# PWR.net
KiCad netlist of a schematic drawn in Altium Designer
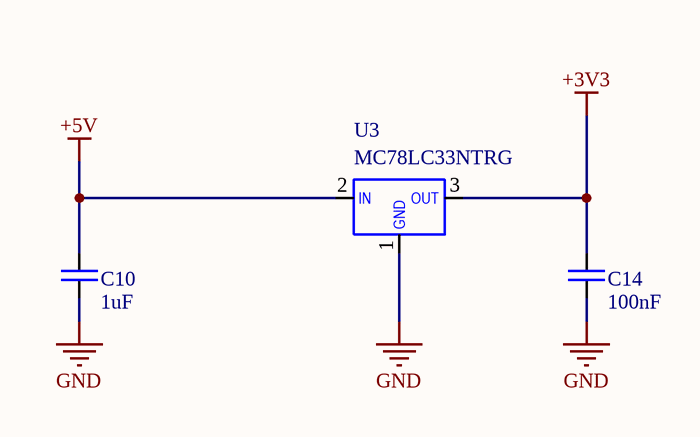
[diagram p0: PWR.SchDoc]

(export (version "E")
  (design (tool "Eeschema 10.0.6"))
  (components
    (comp (ref "C10")
      (value "1uF")
      (footprint "CAP_0603")
      (description "None polar capacitor")
      (libsource (lib "DISCRETE") (part "C_NONE_POLAR"))
    )
    (comp (ref "C14")
      (value "100nF")
      (footprint "CAP_0603")
      (description "None polar capacitor")
      (libsource (lib "DISCRETE") (part "C_NONE_POLAR"))
    )
    (comp (ref "U3")
      (value "MC78LC33NTRG")
      (footprint "ICs:SOT753")
      (description "Low dropout Linear Voltage Regulator")
      (libsource (lib "ICs") (part "MC78LC33NTRG"))
    )
  )
  (nets
    (net (code "1") (name "+3V3") (class "Default")
      (node (ref "C14") (pin "1") (pintype "passive"))
      (node (ref "U3") (pin "3") (pinfunction "OUT_3") (pintype "power_in"))
    )
    (net (code "2") (name "+5V") (class "Default")
      (node (ref "C10") (pin "1") (pintype "passive"))
      (node (ref "U3") (pin "2") (pinfunction "IN_2") (pintype "power_in"))
    )
    (net (code "3") (name "GND") (class "Default")
      (node (ref "C10") (pin "2") (pintype "passive"))
      (node (ref "C14") (pin "2") (pintype "passive"))
      (node (ref "U3") (pin "1") (pinfunction "GND_1") (pintype "passive"))
    )
  )
)
